# jtag_pin_convert.net
KiCad netlist of a schematic drawn in EasyEDA Pro
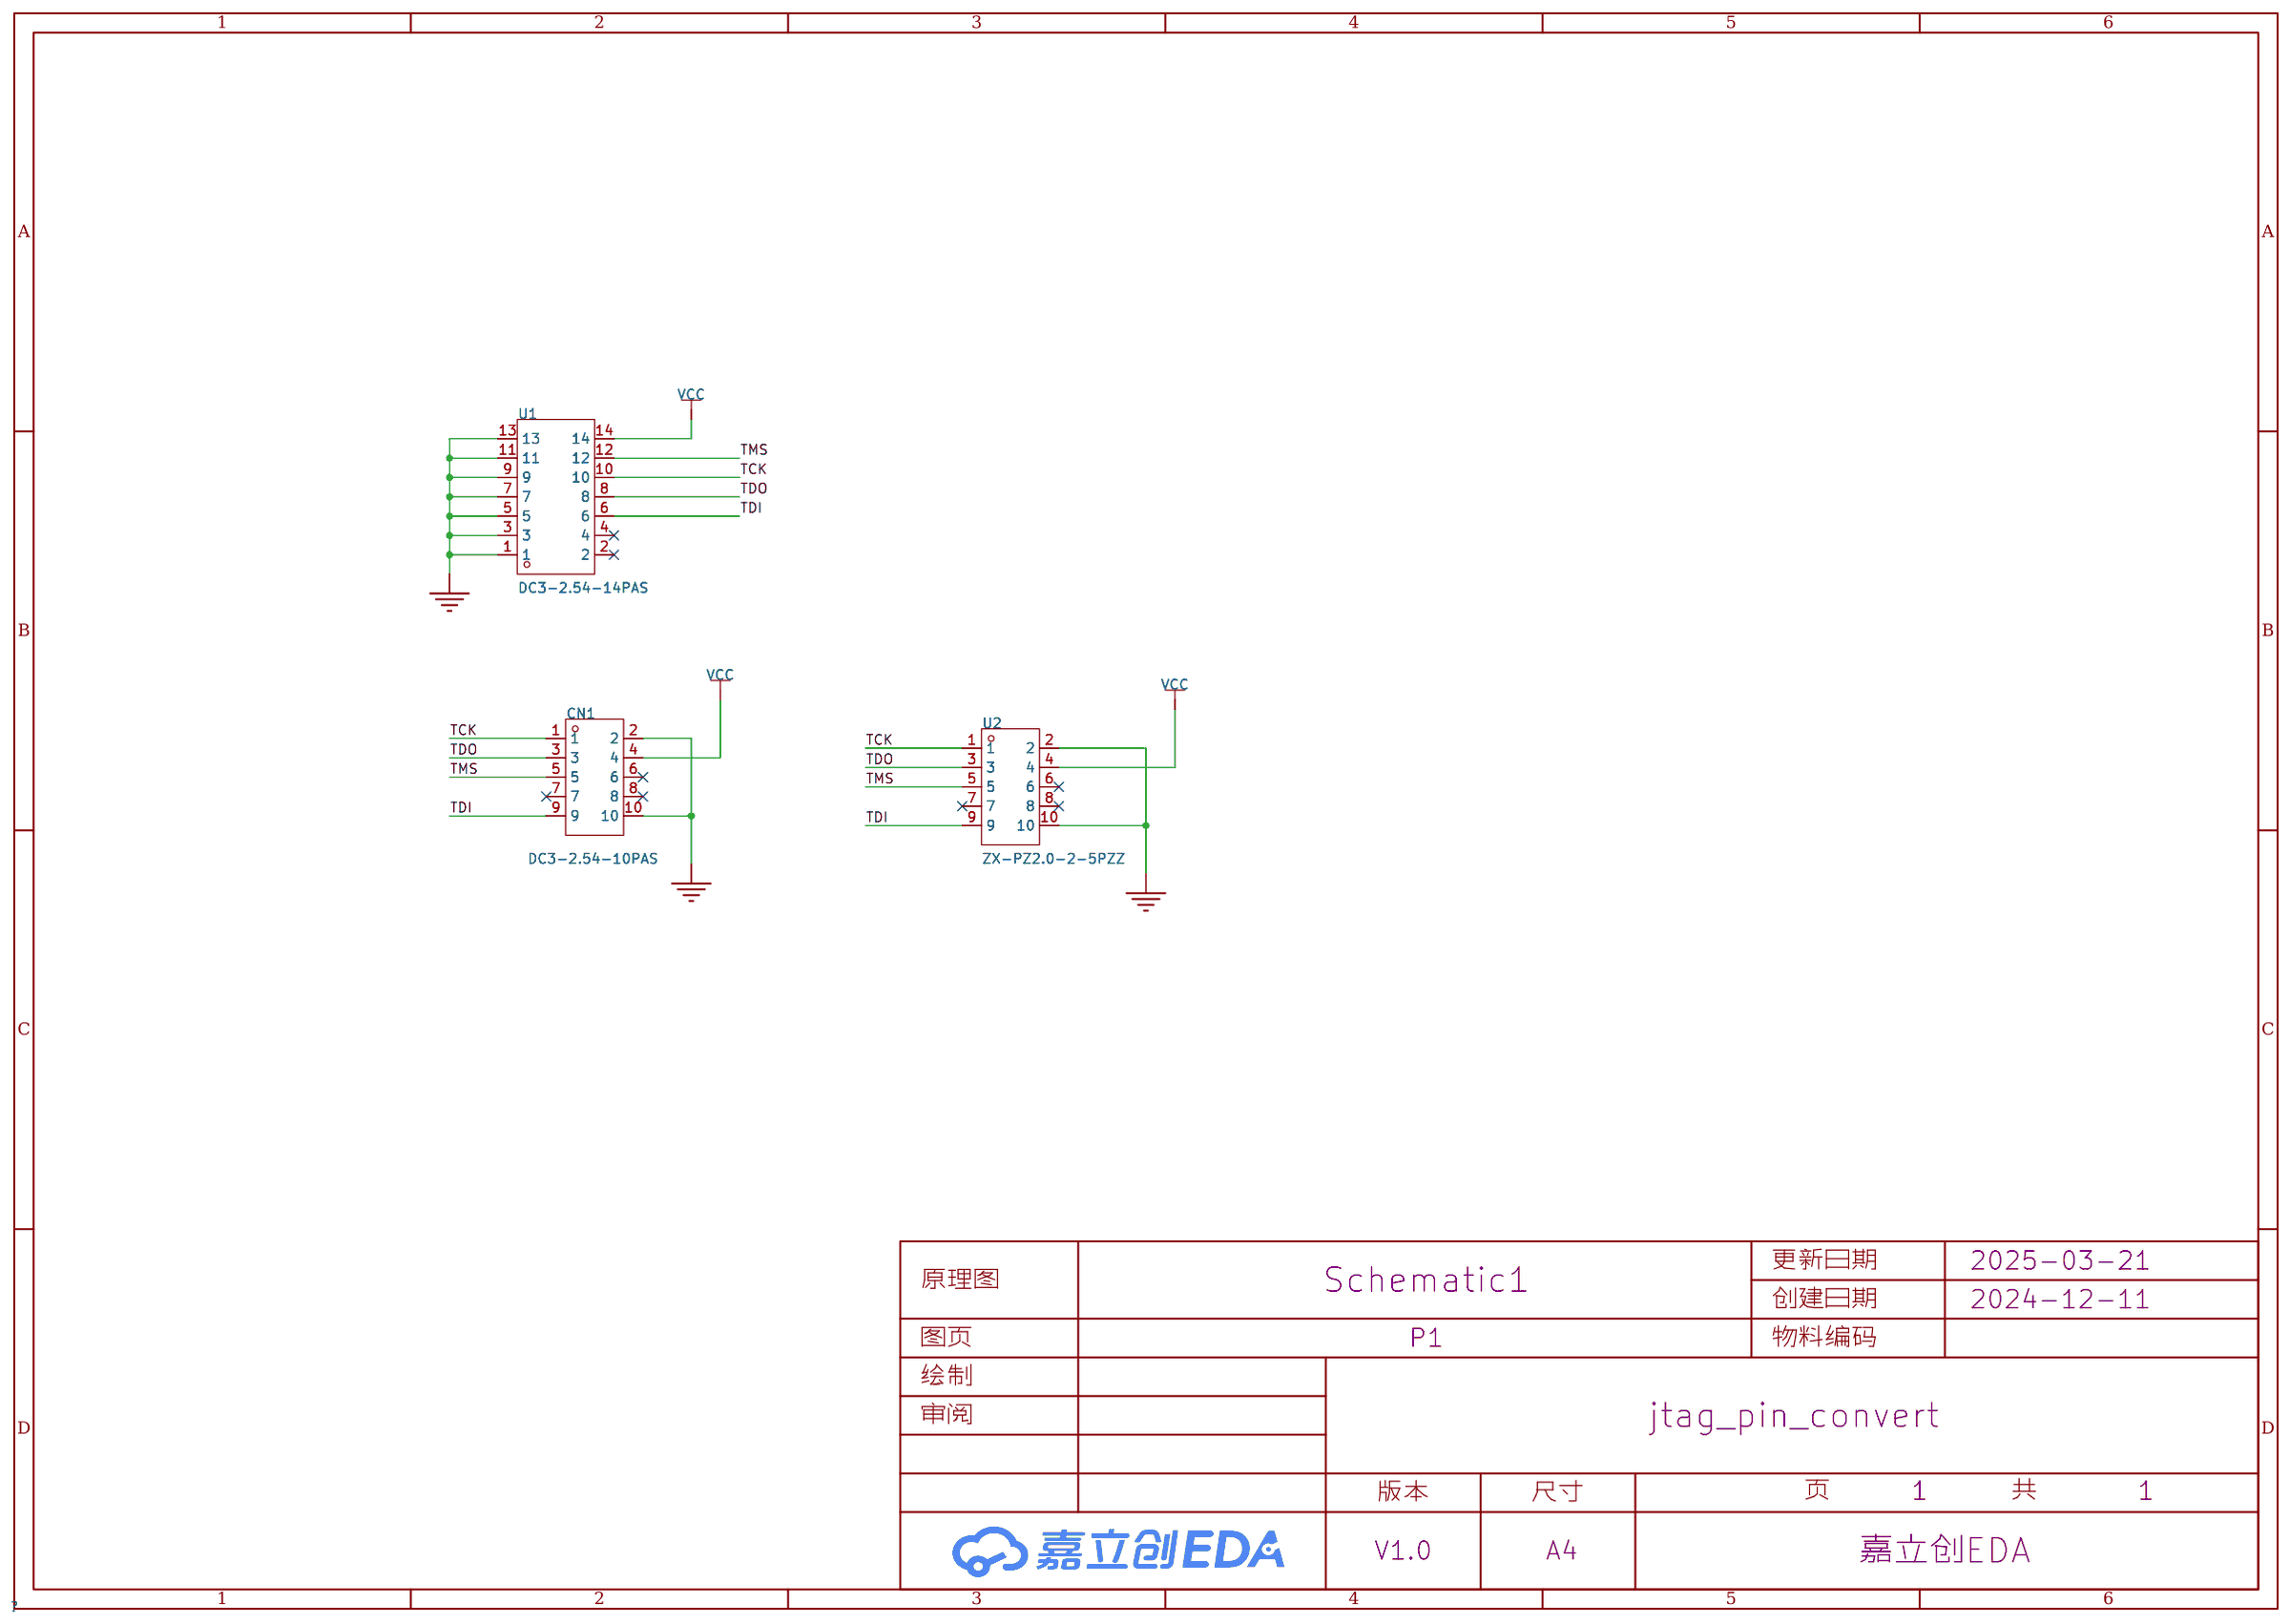
[diagram p0: schematic sheet]

(export (version "E")
  (design (tool "Eeschema 10.0.6"))
  (components
    (comp (ref "CN1")
      (value "DC3-2.54-10PAS")
      (footprint "easyedapro:CONN-TH_10P-P2.54_DC3-2.54-10PAS")
      (description "连接器类型:简牛座;间距:2.54mm;结构:2x5P;额定电流:1.5A;额定电压:-;封装形式:直插;行距:2.54mm;排数:2;每排PIN数:5;工作温度范围:-40°C~+105°C;")
      (fields (field (name "Manufacturer") "ZHOURI(洲日)"))
      (libsource (lib "easyedapro") (part "DC3-2.54-10PAS"))
    )
    (comp (ref "U1")
      (value "DC3-2.54-14PAS")
      (footprint "easyedapro:IDC-TH_14P-P2.54_DC3-2.54-14PAS")
      (description "连接器类型:简牛座;间距:2.54mm;结构:2x7P;额定电流:1.5A;额定电压:-;封装形式:直插;行距:2.54mm;排数:2;每排PIN数:7;工作温度范围:-40°C~+105°C;")
      (fields (field (name "Manufacturer") "ZHOURI(洲日)"))
      (libsource (lib "easyedapro") (part "DC3-2.54-14PAS"))
    )
    (comp (ref "U2")
      (value "ZX-PZ2.0-2-5PZZ")
      (footprint "easyedapro:HDR-TH_10P-P2.00-V-M-R2-C5-S2.00")
      (fields (field (name "Manufacturer") "Megastar(兆星)"))
      (libsource (lib "easyedapro") (part "ZX-PZ2.0-2-5PZZ"))
    )
  )
  (nets
    (net (code "1") (name "/TCK") (class "Default")
      (node (ref "CN1") (pin "1") (pinfunction "1_1") (pintype "unspecified"))
      (node (ref "U1") (pin "10") (pinfunction "10_10") (pintype "unspecified"))
      (node (ref "U2") (pin "1") (pinfunction "1_1") (pintype "unspecified"))
    )
    (net (code "2") (name "/TDI") (class "Default")
      (node (ref "CN1") (pin "9") (pinfunction "9_9") (pintype "unspecified"))
      (node (ref "U1") (pin "6") (pinfunction "6_6") (pintype "unspecified"))
      (node (ref "U2") (pin "9") (pinfunction "9_9") (pintype "unspecified"))
    )
    (net (code "3") (name "/TDO") (class "Default")
      (node (ref "CN1") (pin "3") (pinfunction "3_3") (pintype "unspecified"))
      (node (ref "U1") (pin "8") (pinfunction "8_8") (pintype "unspecified"))
      (node (ref "U2") (pin "3") (pinfunction "3_3") (pintype "unspecified"))
    )
    (net (code "4") (name "/TMS") (class "Default")
      (node (ref "CN1") (pin "5") (pinfunction "5_5") (pintype "unspecified"))
      (node (ref "U1") (pin "12") (pinfunction "12_12") (pintype "unspecified"))
      (node (ref "U2") (pin "5") (pinfunction "5_5") (pintype "unspecified"))
    )
    (net (code "5") (name "GND") (class "Default")
      (node (ref "CN1") (pin "10") (pinfunction "10_10") (pintype "unspecified"))
      (node (ref "CN1") (pin "2") (pinfunction "2_2") (pintype "unspecified"))
      (node (ref "U1") (pin "1") (pinfunction "1_1") (pintype "unspecified"))
      (node (ref "U1") (pin "11") (pinfunction "11_11") (pintype "unspecified"))
      (node (ref "U1") (pin "13") (pinfunction "13_13") (pintype "unspecified"))
      (node (ref "U1") (pin "3") (pinfunction "3_3") (pintype "unspecified"))
      (node (ref "U1") (pin "5") (pinfunction "5_5") (pintype "unspecified"))
      (node (ref "U1") (pin "7") (pinfunction "7_7") (pintype "unspecified"))
      (node (ref "U1") (pin "9") (pinfunction "9_9") (pintype "unspecified"))
      (node (ref "U2") (pin "10") (pinfunction "10_10") (pintype "unspecified"))
      (node (ref "U2") (pin "2") (pinfunction "2_2") (pintype "unspecified"))
    )
    (net (code "6") (name "VCC") (class "Default")
      (node (ref "CN1") (pin "4") (pinfunction "4_4") (pintype "unspecified"))
      (node (ref "U1") (pin "14") (pinfunction "14_14") (pintype "unspecified"))
      (node (ref "U2") (pin "4") (pinfunction "4_4") (pintype "unspecified"))
    )
    (net (code "7") (name "unconnected-(CN1-Pad6)") (class "Default")
      (node (ref "CN1") (pin "6") (pinfunction "6_6") (pintype "unspecified+no_connect"))
    )
    (net (code "8") (name "unconnected-(CN1-Pad7)") (class "Default")
      (node (ref "CN1") (pin "7") (pinfunction "7_7") (pintype "unspecified+no_connect"))
    )
    (net (code "9") (name "unconnected-(CN1-Pad8)") (class "Default")
      (node (ref "CN1") (pin "8") (pinfunction "8_8") (pintype "unspecified+no_connect"))
    )
    (net (code "10") (name "unconnected-(U1-Pad2)") (class "Default")
      (node (ref "U1") (pin "2") (pinfunction "2_2") (pintype "unspecified+no_connect"))
    )
    (net (code "11") (name "unconnected-(U1-Pad4)") (class "Default")
      (node (ref "U1") (pin "4") (pinfunction "4_4") (pintype "unspecified+no_connect"))
    )
    (net (code "12") (name "unconnected-(U2-Pad6)") (class "Default")
      (node (ref "U2") (pin "6") (pinfunction "6_6") (pintype "unspecified+no_connect"))
    )
    (net (code "13") (name "unconnected-(U2-Pad7)") (class "Default")
      (node (ref "U2") (pin "7") (pinfunction "7_7") (pintype "unspecified+no_connect"))
    )
    (net (code "14") (name "unconnected-(U2-Pad8)") (class "Default")
      (node (ref "U2") (pin "8") (pinfunction "8_8") (pintype "unspecified+no_connect"))
    )
  )
)
